# TempSensor.net
KiCad netlist of a schematic drawn in Altium Designer
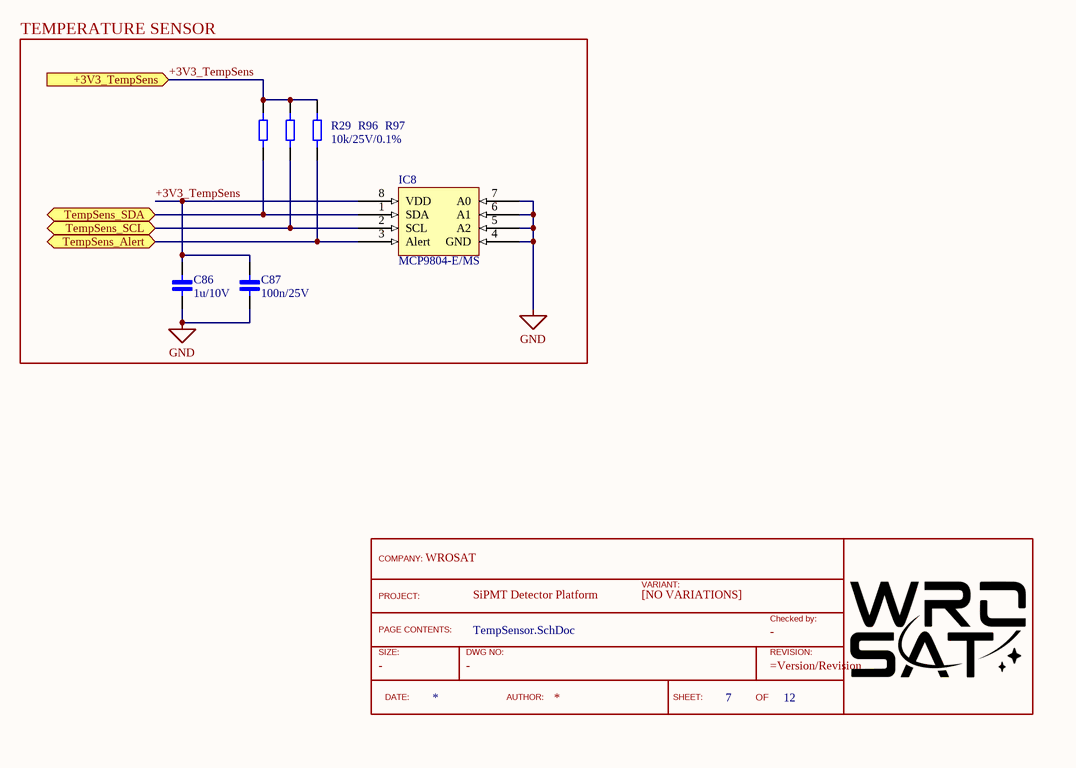
[diagram p0: TempSensor.SchDoc]

(export (version "E")
  (design (tool "Eeschema 10.0.6"))
  (components
    (comp (ref "C86")
      (value "1u/10V")
      (footprint "Cap_0402")
      (description "Ceramic Capacitor 1uF / 0402 / 10V / ±5%, Wurth Elektronik MLCC")
      (libsource (lib "WroSat_Passive_components") (part "Cap_0402_1u"))
    )
    (comp (ref "C87")
      (value "100n/25V")
      (footprint "Cap_0402")
      (description "Ceramic Capacitor 100n / 0402 / 25V / ±5%, Wurth Elektronik MLCC")
      (libsource (lib "WroSat_Passive_components") (part "Cap_0402_100n"))
    )
    (comp (ref "IC8")
      (value "MCP9804-E/MS")
      (footprint "MSOP-8")
      (description "Temp Sensor Digital Serial (2-Wire) Automotive 8-Pin MSOP")
      (fields (field (name "MANUFACTURER") "Microchip"))
      (libsource (lib "WroSat_Integrated_circuits") (part "MCP9804-E/MS"))
    )
    (comp (ref "R29")
      (value "10k/25V/0.1%")
      (footprint "RES_0402")
      (description "Vishay, thin film resistor 10k/25V/0.1%")
      (libsource (lib "WroSat_Passive_components") (part "Res_0402_10k"))
    )
    (comp (ref "R96")
      (value "10k/25V/0.1%")
      (footprint "RES_0402")
      (description "Vishay, thin film resistor 10k/25V/0.1%")
      (libsource (lib "WroSat_Passive_components") (part "Res_0402_10k"))
    )
    (comp (ref "R97")
      (value "10k/25V/0.1%")
      (footprint "RES_0402")
      (description "Vishay, thin film resistor 10k/25V/0.1%")
      (libsource (lib "WroSat_Passive_components") (part "Res_0402_10k"))
    )
  )
  (nets
    (net (code "1") (name "/+3V3_TempSens") (class "Default")
      (node (ref "C86") (pin "2") (pinfunction "2_2") (pintype "passive"))
      (node (ref "C87") (pin "2") (pinfunction "2_2") (pintype "passive"))
      (node (ref "IC8") (pin "8") (pinfunction "VDD_8") (pintype "input"))
      (node (ref "R29") (pin "2") (pinfunction "2_2") (pintype "passive"))
      (node (ref "R96") (pin "2") (pinfunction "2_2") (pintype "passive"))
      (node (ref "R97") (pin "2") (pinfunction "2_2") (pintype "passive"))
    )
    (net (code "2") (name "/TempSens_Alert") (class "Default")
      (node (ref "IC8") (pin "3") (pinfunction "Alert_3") (pintype "input"))
      (node (ref "R97") (pin "1") (pinfunction "1_1") (pintype "passive"))
    )
    (net (code "3") (name "/TempSens_SCL") (class "Default")
      (node (ref "IC8") (pin "2") (pinfunction "SCL_2") (pintype "input"))
      (node (ref "R96") (pin "1") (pinfunction "1_1") (pintype "passive"))
    )
    (net (code "4") (name "/TempSens_SDA") (class "Default")
      (node (ref "IC8") (pin "1") (pinfunction "SDA_1") (pintype "input"))
      (node (ref "R29") (pin "1") (pinfunction "1_1") (pintype "passive"))
    )
    (net (code "5") (name "GND") (class "Default")
      (node (ref "C86") (pin "1") (pinfunction "1_1") (pintype "passive"))
      (node (ref "C87") (pin "1") (pinfunction "1_1") (pintype "passive"))
      (node (ref "IC8") (pin "4") (pinfunction "GND_4") (pintype "input"))
      (node (ref "IC8") (pin "5") (pinfunction "A2_5") (pintype "input"))
      (node (ref "IC8") (pin "6") (pinfunction "A1_6") (pintype "input"))
      (node (ref "IC8") (pin "7") (pinfunction "A0_7") (pintype "input"))
    )
  )
)
